# Reader32chv2.net
KiCad netlist of a schematic drawn in Altium Designer
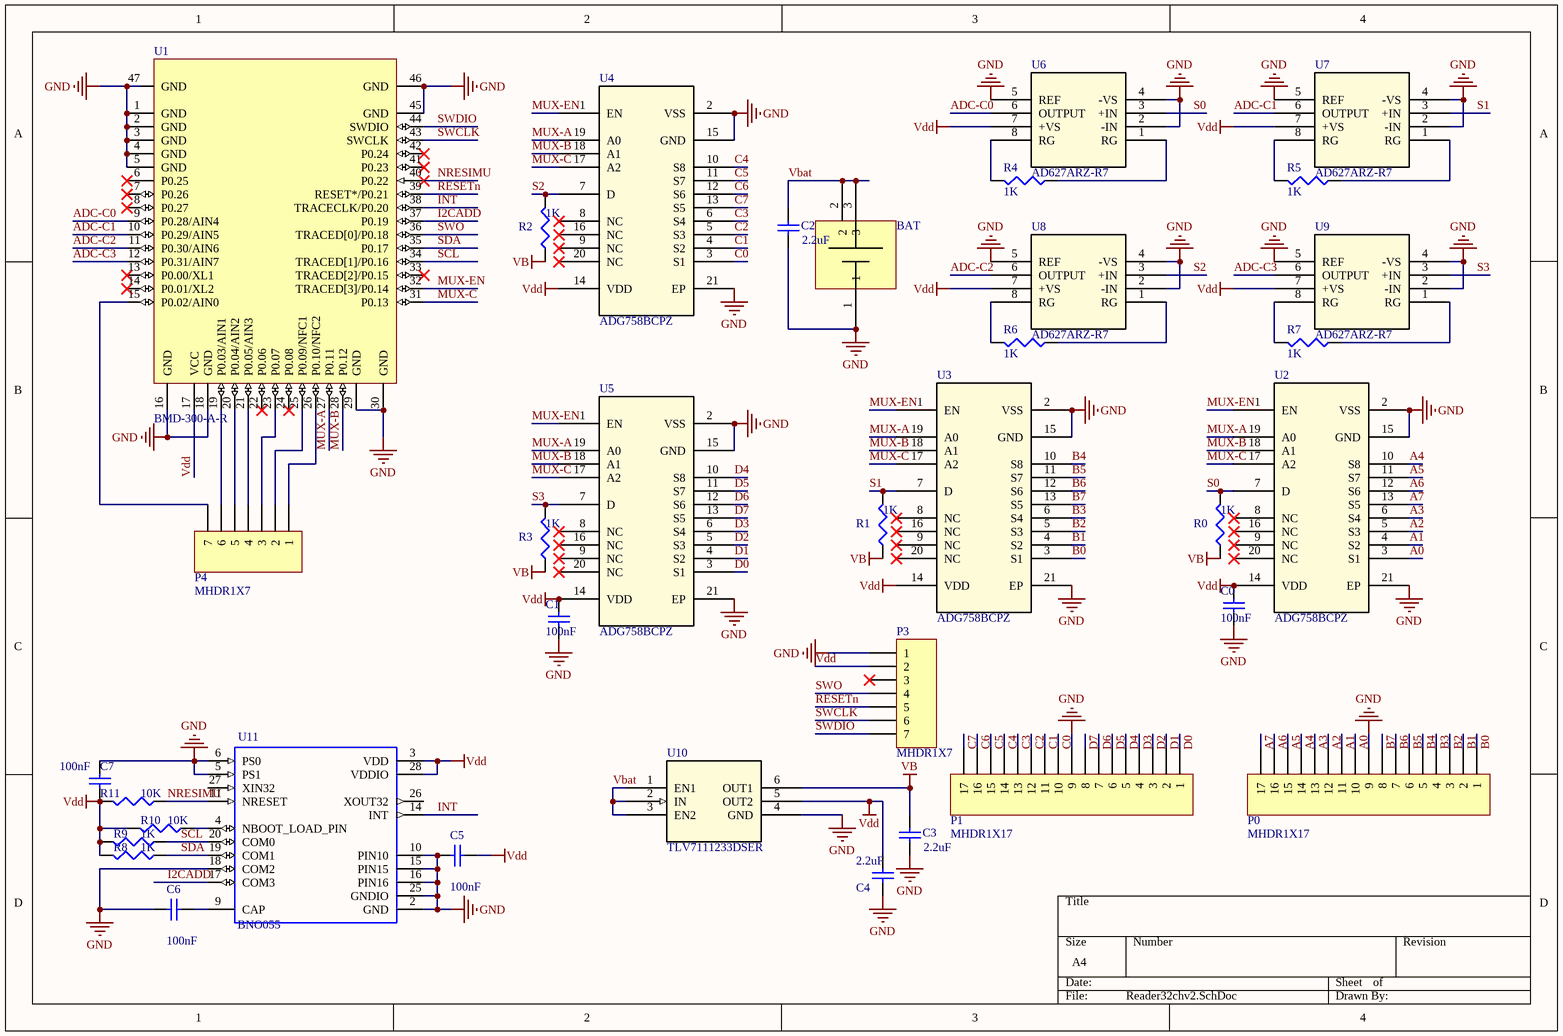
[diagram p0: Reader32chv2.SchDoc]

(export (version "E")
  (design (tool "Eeschema 10.0.6"))
  (components
    (comp (ref "BAT") (value "~") (footprint "BU-2032") (libsource (lib "My_Library") (part "BT")))
    (comp (ref "C0")
      (value "100nF")
      (footprint "1608[0603]")
      (description "Capacitor (Semiconductor SIM Model)")
      (fields (field (name "PUBLISHER") "Altium Limited"))
      (libsource (lib "Miscellaneous Devices") (part "Cap Semi"))
    )
    (comp (ref "C1")
      (value "100nF")
      (footprint "1608[0603]")
      (description "Capacitor (Semiconductor SIM Model)")
      (fields (field (name "PUBLISHER") "Altium Limited"))
      (libsource (lib "Miscellaneous Devices") (part "Cap Semi"))
    )
    (comp (ref "C2")
      (value "2.2uF")
      (footprint "1608[0603]")
      (description "Capacitor (Semiconductor SIM Model)")
      (fields (field (name "PUBLISHER") "Altium Limited"))
      (libsource (lib "Miscellaneous Devices") (part "Cap Semi"))
    )
    (comp (ref "C3")
      (value "2.2uF")
      (footprint "1608[0603]")
      (description "Capacitor (Semiconductor SIM Model)")
      (fields (field (name "PUBLISHER") "Altium Limited"))
      (libsource (lib "Miscellaneous Devices") (part "Cap Semi"))
    )
    (comp (ref "C4")
      (value "2.2uF")
      (footprint "1608[0603]")
      (description "Capacitor (Semiconductor SIM Model)")
      (fields (field (name "PUBLISHER") "Altium Limited"))
      (libsource (lib "Miscellaneous Devices") (part "Cap Semi"))
    )
    (comp (ref "C5")
      (value "100nF")
      (footprint "1608[0603]")
      (description "Capacitor (Semiconductor SIM Model)")
      (fields (field (name "PUBLISHER") "Altium Limited"))
      (libsource (lib "Miscellaneous Devices") (part "Cap Semi"))
    )
    (comp (ref "C6")
      (value "100nF")
      (footprint "1608[0603]")
      (description "Capacitor (Semiconductor SIM Model)")
      (fields (field (name "PUBLISHER") "Altium Limited"))
      (libsource (lib "Miscellaneous Devices") (part "Cap Semi"))
    )
    (comp (ref "C7")
      (value "100nF")
      (footprint "1608[0603]")
      (description "Capacitor (Semiconductor SIM Model)")
      (fields (field (name "PUBLISHER") "Altium Limited"))
      (libsource (lib "Miscellaneous Devices") (part "Cap Semi"))
    )
    (comp (ref "P0")
      (value "MHDR1X17")
      (footprint "MHDR1X17")
      (description "Header, 17-Pin")
      (fields (field (name "PUBLISHER") "Altium Limited"))
      (libsource (lib "Miscellaneous Connectors") (part "MHDR1X17"))
    )
    (comp (ref "P1")
      (value "MHDR1X17")
      (footprint "MHDR1X17")
      (description "Header, 17-Pin")
      (fields (field (name "PUBLISHER") "Altium Limited"))
      (libsource (lib "Miscellaneous Connectors") (part "MHDR1X17"))
    )
    (comp (ref "P3")
      (value "MHDR1X7")
      (footprint "MHDR1X7")
      (description "Header, 7-Pin")
      (fields (field (name "PUBLISHER") "Altium Limited"))
      (libsource (lib "Miscellaneous Connectors") (part "MHDR1X7"))
    )
    (comp (ref "P4")
      (value "MHDR1X7")
      (footprint "MHDR1X7")
      (description "Header, 7-Pin")
      (fields (field (name "PUBLISHER") "Altium Limited"))
      (libsource (lib "") (part "MHDR1X7_1"))
    )
    (comp (ref "R0")
      (value "1K")
      (footprint "J1-0603")
      (description "Resistor")
      (fields (field (name "PUBLISHER") "Altium Limited"))
      (libsource (lib "Miscellaneous Devices") (part "Res3"))
    )
    (comp (ref "R1")
      (value "1K")
      (footprint "J1-0603")
      (description "Resistor")
      (fields (field (name "PUBLISHER") "Altium Limited"))
      (libsource (lib "Miscellaneous Devices") (part "Res3"))
    )
    (comp (ref "R2")
      (value "1K")
      (footprint "J1-0603")
      (description "Resistor")
      (fields (field (name "PUBLISHER") "Altium Limited"))
      (libsource (lib "Miscellaneous Devices") (part "Res3"))
    )
    (comp (ref "R3")
      (value "1K")
      (footprint "J1-0603")
      (description "Resistor")
      (fields (field (name "PUBLISHER") "Altium Limited"))
      (libsource (lib "Miscellaneous Devices") (part "Res3"))
    )
    (comp (ref "R4")
      (value "1K")
      (footprint "J1-0603")
      (description "Resistor")
      (fields (field (name "PUBLISHER") "Altium Limited"))
      (libsource (lib "Miscellaneous Devices") (part "Res3"))
    )
    (comp (ref "R5")
      (value "1K")
      (footprint "J1-0603")
      (description "Resistor")
      (fields (field (name "PUBLISHER") "Altium Limited"))
      (libsource (lib "Miscellaneous Devices") (part "Res3"))
    )
    (comp (ref "R6")
      (value "1K")
      (footprint "J1-0603")
      (description "Resistor")
      (fields (field (name "PUBLISHER") "Altium Limited"))
      (libsource (lib "Miscellaneous Devices") (part "Res3"))
    )
    (comp (ref "R7")
      (value "1K")
      (footprint "J1-0603")
      (description "Resistor")
      (fields (field (name "PUBLISHER") "Altium Limited"))
      (libsource (lib "Miscellaneous Devices") (part "Res3"))
    )
    (comp (ref "R8")
      (value "1K")
      (footprint "J1-0603")
      (description "Resistor")
      (fields (field (name "PUBLISHER") "Altium Limited"))
      (libsource (lib "Miscellaneous Devices") (part "Res3"))
    )
    (comp (ref "R9")
      (value "1K")
      (footprint "J1-0603")
      (description "Resistor")
      (fields (field (name "PUBLISHER") "Altium Limited"))
      (libsource (lib "Miscellaneous Devices") (part "Res3"))
    )
    (comp (ref "R10")
      (value "10K")
      (footprint "J1-0603")
      (description "Resistor")
      (fields (field (name "PUBLISHER") "Altium Limited"))
      (libsource (lib "Miscellaneous Devices") (part "Res3"))
    )
    (comp (ref "R11")
      (value "10K")
      (footprint "J1-0603")
      (description "Resistor")
      (fields (field (name "PUBLISHER") "Altium Limited"))
      (libsource (lib "Miscellaneous Devices") (part "Res3"))
    )
    (comp (ref "U1")
      (value "BMD-300")
      (footprint "BMD-300")
      (description "Bluetooth 4.2 LE Module, nRF52832, 512kB Flash, 64kB RAM")
      (fields
        (field (name "PART NUMBER") "BMD-300-A")
        (field (name "MANUFACTURER") "Rigado")
        (field (name "MANUFACTURER P/N") "BMD-300-A-R")
        (field (name "ADDED BY") "Cam N")
      )
      (libsource (lib "BMD-300-Altium") (part "BMD-300-A"))
    )
    (comp (ref "U2")
      (value "ADG758BCPZ")
      (footprint "CP_20_6")
      (description "Imported")
      (libsource (lib "2017-12-08_19-39-35") (part "ADG758BCPZ"))
    )
    (comp (ref "U3")
      (value "ADG758BCPZ")
      (footprint "CP_20_6")
      (description "Imported")
      (libsource (lib "2017-12-08_19-39-35") (part "ADG758BCPZ"))
    )
    (comp (ref "U4")
      (value "ADG758BCPZ")
      (footprint "CP_20_6")
      (description "Imported")
      (libsource (lib "2017-12-08_19-39-35") (part "ADG758BCPZ"))
    )
    (comp (ref "U5")
      (value "ADG758BCPZ")
      (footprint "CP_20_6")
      (description "Imported")
      (libsource (lib "2017-12-08_19-39-35") (part "ADG758BCPZ"))
    )
    (comp (ref "U6")
      (value "AD627ARZ-R7")
      (footprint "AltiumDesigner:R_8")
      (description "Imported")
      (libsource (lib "AltiumDesigner") (part "AD627ARZ-R7"))
    )
    (comp (ref "U7")
      (value "AD627ARZ-R7")
      (footprint "AltiumDesigner:R_8")
      (description "Imported")
      (libsource (lib "AltiumDesigner") (part "AD627ARZ-R7"))
    )
    (comp (ref "U8")
      (value "AD627ARZ-R7")
      (footprint "AltiumDesigner:R_8")
      (description "Imported")
      (libsource (lib "AltiumDesigner") (part "AD627ARZ-R7"))
    )
    (comp (ref "U9")
      (value "AD627ARZ-R7")
      (footprint "AltiumDesigner:R_8")
      (description "Imported")
      (libsource (lib "AltiumDesigner") (part "AD627ARZ-R7"))
    )
    (comp (ref "U10")
      (value "TLV7111233DSER")
      (footprint "AltiumDesigner:DSE6")
      (description "Imported")
      (fields (field (name "MANUFACTURER") "Texas Instruments"))
      (libsource (lib "AltiumDesigner") (part "TLV7111233DSER"))
    )
    (comp (ref "U11")
      (value "BNO055")
      (footprint "LGA28R50P4X10_380X520X100")
      (description "BNO055 9-axis Absolute Orientation Sensor _ SiP _ w/Sensors and Sensor Fusion")
      (fields (field (name "MF") "Bosch"))
      (libsource (lib "BNO055") (part "BNO055"))
    )
  )
  (nets
    (net (code "1") (name "/A0") (class "Default")
      (node (ref "P0") (pin "10") (pinfunction "10_10") (pintype "passive"))
      (node (ref "U2") (pin "3") (pinfunction "S1_3") (pintype "passive"))
    )
    (net (code "2") (name "/A1") (class "Default")
      (node (ref "P0") (pin "11") (pinfunction "11_11") (pintype "passive"))
      (node (ref "U2") (pin "4") (pinfunction "S2_4") (pintype "passive"))
    )
    (net (code "3") (name "/A2") (class "Default")
      (node (ref "P0") (pin "12") (pinfunction "12_12") (pintype "passive"))
      (node (ref "U2") (pin "5") (pinfunction "S3_5") (pintype "passive"))
    )
    (net (code "4") (name "/A3") (class "Default")
      (node (ref "P0") (pin "13") (pinfunction "13_13") (pintype "passive"))
      (node (ref "U2") (pin "6") (pinfunction "S4_6") (pintype "passive"))
    )
    (net (code "5") (name "/A4") (class "Default")
      (node (ref "P0") (pin "14") (pinfunction "14_14") (pintype "passive"))
      (node (ref "U2") (pin "10") (pinfunction "S8_10") (pintype "passive"))
    )
    (net (code "6") (name "/A5") (class "Default")
      (node (ref "P0") (pin "15") (pinfunction "15_15") (pintype "passive"))
      (node (ref "U2") (pin "11") (pinfunction "S7_11") (pintype "passive"))
    )
    (net (code "7") (name "/A6") (class "Default")
      (node (ref "P0") (pin "16") (pinfunction "16_16") (pintype "passive"))
      (node (ref "U2") (pin "12") (pinfunction "S6_12") (pintype "passive"))
    )
    (net (code "8") (name "/A7") (class "Default")
      (node (ref "P0") (pin "17") (pinfunction "17_17") (pintype "passive"))
      (node (ref "U2") (pin "13") (pinfunction "S5_13") (pintype "passive"))
    )
    (net (code "9") (name "/ADC-C0") (class "Default")
      (node (ref "U1") (pin "9") (pinfunction "P0.28/AIN4_9") (pintype "bidirectional"))
      (node (ref "U6") (pin "6") (pinfunction "OUTPUT_6") (pintype "passive"))
    )
    (net (code "10") (name "/ADC-C1") (class "Default")
      (node (ref "U1") (pin "10") (pinfunction "P0.29/AIN5_10") (pintype "bidirectional"))
      (node (ref "U7") (pin "6") (pinfunction "OUTPUT_6") (pintype "passive"))
    )
    (net (code "11") (name "/ADC-C2") (class "Default")
      (node (ref "U1") (pin "11") (pinfunction "P0.30/AIN6_11") (pintype "bidirectional"))
      (node (ref "U8") (pin "6") (pinfunction "OUTPUT_6") (pintype "passive"))
    )
    (net (code "12") (name "/ADC-C3") (class "Default")
      (node (ref "U1") (pin "12") (pinfunction "P0.31/AIN7_12") (pintype "bidirectional"))
      (node (ref "U9") (pin "6") (pinfunction "OUTPUT_6") (pintype "passive"))
    )
    (net (code "13") (name "/B0") (class "Default")
      (node (ref "P0") (pin "1") (pinfunction "1_1") (pintype "passive"))
      (node (ref "U3") (pin "3") (pinfunction "S1_3") (pintype "passive"))
    )
    (net (code "14") (name "/B1") (class "Default")
      (node (ref "P0") (pin "2") (pinfunction "2_2") (pintype "passive"))
      (node (ref "U3") (pin "4") (pinfunction "S2_4") (pintype "passive"))
    )
    (net (code "15") (name "/B2") (class "Default")
      (node (ref "P0") (pin "3") (pinfunction "3_3") (pintype "passive"))
      (node (ref "U3") (pin "5") (pinfunction "S3_5") (pintype "passive"))
    )
    (net (code "16") (name "/B3") (class "Default")
      (node (ref "P0") (pin "4") (pinfunction "4_4") (pintype "passive"))
      (node (ref "U3") (pin "6") (pinfunction "S4_6") (pintype "passive"))
    )
    (net (code "17") (name "/B4") (class "Default")
      (node (ref "P0") (pin "5") (pinfunction "5_5") (pintype "passive"))
      (node (ref "U3") (pin "10") (pinfunction "S8_10") (pintype "passive"))
    )
    (net (code "18") (name "/B5") (class "Default")
      (node (ref "P0") (pin "6") (pinfunction "6_6") (pintype "passive"))
      (node (ref "U3") (pin "11") (pinfunction "S7_11") (pintype "passive"))
    )
    (net (code "19") (name "/B6") (class "Default")
      (node (ref "P0") (pin "7") (pinfunction "7_7") (pintype "passive"))
      (node (ref "U3") (pin "12") (pinfunction "S6_12") (pintype "passive"))
    )
    (net (code "20") (name "/B7") (class "Default")
      (node (ref "P0") (pin "8") (pinfunction "8_8") (pintype "passive"))
      (node (ref "U3") (pin "13") (pinfunction "S5_13") (pintype "passive"))
    )
    (net (code "21") (name "/C0") (class "Default")
      (node (ref "P1") (pin "10") (pinfunction "10_10") (pintype "passive"))
      (node (ref "U4") (pin "3") (pinfunction "S1_3") (pintype "passive"))
    )
    (net (code "22") (name "/C1") (class "Default")
      (node (ref "P1") (pin "11") (pinfunction "11_11") (pintype "passive"))
      (node (ref "U4") (pin "4") (pinfunction "S2_4") (pintype "passive"))
    )
    (net (code "23") (name "/C2") (class "Default")
      (node (ref "P1") (pin "12") (pinfunction "12_12") (pintype "passive"))
      (node (ref "U4") (pin "5") (pinfunction "S3_5") (pintype "passive"))
    )
    (net (code "24") (name "/C3") (class "Default")
      (node (ref "P1") (pin "13") (pinfunction "13_13") (pintype "passive"))
      (node (ref "U4") (pin "6") (pinfunction "S4_6") (pintype "passive"))
    )
    (net (code "25") (name "/C4") (class "Default")
      (node (ref "P1") (pin "14") (pinfunction "14_14") (pintype "passive"))
      (node (ref "U4") (pin "10") (pinfunction "S8_10") (pintype "passive"))
    )
    (net (code "26") (name "/C5") (class "Default")
      (node (ref "P1") (pin "15") (pinfunction "15_15") (pintype "passive"))
      (node (ref "U4") (pin "11") (pinfunction "S7_11") (pintype "passive"))
    )
    (net (code "27") (name "/C6") (class "Default")
      (node (ref "P1") (pin "16") (pinfunction "16_16") (pintype "passive"))
      (node (ref "U4") (pin "12") (pinfunction "S6_12") (pintype "passive"))
    )
    (net (code "28") (name "/C7") (class "Default")
      (node (ref "P1") (pin "17") (pinfunction "17_17") (pintype "passive"))
      (node (ref "U4") (pin "13") (pinfunction "S5_13") (pintype "passive"))
    )
    (net (code "29") (name "/D0") (class "Default")
      (node (ref "P1") (pin "1") (pinfunction "1_1") (pintype "passive"))
      (node (ref "U5") (pin "3") (pinfunction "S1_3") (pintype "passive"))
    )
    (net (code "30") (name "/D1") (class "Default")
      (node (ref "P1") (pin "2") (pinfunction "2_2") (pintype "passive"))
      (node (ref "U5") (pin "4") (pinfunction "S2_4") (pintype "passive"))
    )
    (net (code "31") (name "/D2") (class "Default")
      (node (ref "P1") (pin "3") (pinfunction "3_3") (pintype "passive"))
      (node (ref "U5") (pin "5") (pinfunction "S3_5") (pintype "passive"))
    )
    (net (code "32") (name "/D3") (class "Default")
      (node (ref "P1") (pin "4") (pinfunction "4_4") (pintype "passive"))
      (node (ref "U5") (pin "6") (pinfunction "S4_6") (pintype "passive"))
    )
    (net (code "33") (name "/D4") (class "Default")
      (node (ref "P1") (pin "5") (pinfunction "5_5") (pintype "passive"))
      (node (ref "U5") (pin "10") (pinfunction "S8_10") (pintype "passive"))
    )
    (net (code "34") (name "/D5") (class "Default")
      (node (ref "P1") (pin "6") (pinfunction "6_6") (pintype "passive"))
      (node (ref "U5") (pin "11") (pinfunction "S7_11") (pintype "passive"))
    )
    (net (code "35") (name "/D6") (class "Default")
      (node (ref "P1") (pin "7") (pinfunction "7_7") (pintype "passive"))
      (node (ref "U5") (pin "12") (pinfunction "S6_12") (pintype "passive"))
    )
    (net (code "36") (name "/D7") (class "Default")
      (node (ref "P1") (pin "8") (pinfunction "8_8") (pintype "passive"))
      (node (ref "U5") (pin "13") (pinfunction "S5_13") (pintype "passive"))
    )
    (net (code "37") (name "/I2CADD") (class "Default")
      (node (ref "U1") (pin "37") (pinfunction "P0.19_37") (pintype "bidirectional"))
      (node (ref "U11") (pin "17") (pinfunction "COM3_17") (pintype "bidirectional"))
    )
    (net (code "38") (name "/INT") (class "Default")
      (node (ref "U1") (pin "38") (pinfunction "TRACECLK/P0.20_38") (pintype "bidirectional"))
      (node (ref "U11") (pin "14") (pinfunction "INT_14") (pintype "output"))
    )
    (net (code "39") (name "/MUX-A") (class "Default")
      (node (ref "U1") (pin "27") (pinfunction "P0.11_27") (pintype "bidirectional"))
      (node (ref "U2") (pin "19") (pinfunction "A0_19") (pintype "passive"))
      (node (ref "U3") (pin "19") (pinfunction "A0_19") (pintype "passive"))
      (node (ref "U4") (pin "19") (pinfunction "A0_19") (pintype "passive"))
      (node (ref "U5") (pin "19") (pinfunction "A0_19") (pintype "passive"))
    )
    (net (code "40") (name "/MUX-B") (class "Default")
      (node (ref "U1") (pin "28") (pinfunction "P0.12_28") (pintype "bidirectional"))
      (node (ref "U2") (pin "18") (pinfunction "A1_18") (pintype "passive"))
      (node (ref "U3") (pin "18") (pinfunction "A1_18") (pintype "passive"))
      (node (ref "U4") (pin "18") (pinfunction "A1_18") (pintype "passive"))
      (node (ref "U5") (pin "18") (pinfunction "A1_18") (pintype "passive"))
    )
    (net (code "41") (name "/MUX-C") (class "Default")
      (node (ref "U1") (pin "31") (pinfunction "P0.13_31") (pintype "bidirectional"))
      (node (ref "U2") (pin "17") (pinfunction "A2_17") (pintype "passive"))
      (node (ref "U3") (pin "17") (pinfunction "A2_17") (pintype "passive"))
      (node (ref "U4") (pin "17") (pinfunction "A2_17") (pintype "passive"))
      (node (ref "U5") (pin "17") (pinfunction "A2_17") (pintype "passive"))
    )
    (net (code "42") (name "/MUX-EN") (class "Default")
      (node (ref "U1") (pin "32") (pinfunction "TRACED[3]/P0.14_32") (pintype "bidirectional"))
      (node (ref "U2") (pin "1") (pinfunction "EN_1") (pintype "passive"))
      (node (ref "U3") (pin "1") (pinfunction "EN_1") (pintype "passive"))
      (node (ref "U4") (pin "1") (pinfunction "EN_1") (pintype "passive"))
      (node (ref "U5") (pin "1") (pinfunction "EN_1") (pintype "passive"))
    )
    (net (code "43") (name "/NRESIMU") (class "Default")
      (node (ref "R11") (pin "1") (pinfunction "1_1") (pintype "passive"))
      (node (ref "U1") (pin "40") (pinfunction "P0.22_40") (pintype "input"))
      (node (ref "U11") (pin "11") (pinfunction "NRESET_11") (pintype "input"))
    )
    (net (code "44") (name "/RESETn") (class "Default")
      (node (ref "P3") (pin "5") (pinfunction "5_5") (pintype "passive"))
      (node (ref "U1") (pin "39") (pinfunction "RESET*/P0.21_39") (pintype "bidirectional"))
    )
    (net (code "45") (name "/S0") (class "Default")
      (node (ref "R0") (pin "2") (pinfunction "2_2") (pintype "passive"))
      (node (ref "U2") (pin "7") (pinfunction "D_7") (pintype "passive"))
      (node (ref "U6") (pin "3") (pinfunction "+IN_3") (pintype "passive"))
    )
    (net (code "46") (name "/S1") (class "Default")
      (node (ref "R1") (pin "2") (pinfunction "2_2") (pintype "passive"))
      (node (ref "U3") (pin "7") (pinfunction "D_7") (pintype "passive"))
      (node (ref "U7") (pin "3") (pinfunction "+IN_3") (pintype "passive"))
    )
    (net (code "47") (name "/S2") (class "Default")
      (node (ref "R2") (pin "2") (pinfunction "2_2") (pintype "passive"))
      (node (ref "U4") (pin "7") (pinfunction "D_7") (pintype "passive"))
      (node (ref "U8") (pin "3") (pinfunction "+IN_3") (pintype "passive"))
    )
    (net (code "48") (name "/S3") (class "Default")
      (node (ref "R3") (pin "2") (pinfunction "2_2") (pintype "passive"))
      (node (ref "U5") (pin "7") (pinfunction "D_7") (pintype "passive"))
      (node (ref "U9") (pin "3") (pinfunction "+IN_3") (pintype "passive"))
    )
    (net (code "49") (name "/SCL") (class "Default")
      (node (ref "R9") (pin "1") (pinfunction "1_1") (pintype "passive"))
      (node (ref "U1") (pin "34") (pinfunction "TRACED[1]/P0.16_34") (pintype "bidirectional"))
      (node (ref "U11") (pin "20") (pinfunction "COM0_20") (pintype "bidirectional"))
    )
    (net (code "50") (name "/SDA") (class "Default")
      (node (ref "R8") (pin "1") (pinfunction "1_1") (pintype "passive"))
      (node (ref "U1") (pin "35") (pinfunction "P0.17_35") (pintype "bidirectional"))
      (node (ref "U11") (pin "19") (pinfunction "COM1_19") (pintype "bidirectional"))
    )
    (net (code "51") (name "/SWCLK") (class "Default")
      (node (ref "P3") (pin "6") (pinfunction "6_6") (pintype "passive"))
      (node (ref "U1") (pin "43") (pinfunction "SWCLK_43") (pintype "bidirectional"))
    )
    (net (code "52") (name "/SWDIO") (class "Default")
      (node (ref "P3") (pin "7") (pinfunction "7_7") (pintype "passive"))
      (node (ref "U1") (pin "44") (pinfunction "SWDIO_44") (pintype "bidirectional"))
    )
    (net (code "53") (name "/SWO") (class "Default")
      (node (ref "P3") (pin "4") (pinfunction "4_4") (pintype "passive"))
      (node (ref "U1") (pin "36") (pinfunction "TRACED[0]/P0.18_36") (pintype "bidirectional"))
    )
    (net (code "54") (name "/Vbat") (class "Default")
      (node (ref "BAT") (pin "2") (pinfunction "2_2") (pintype "passive"))
      (node (ref "BAT") (pin "3") (pinfunction "3_3") (pintype "passive"))
      (node (ref "C2") (pin "2") (pinfunction "2_2") (pintype "passive"))
      (node (ref "U10") (pin "1") (pinfunction "EN1_1") (pintype "passive"))
      (node (ref "U10") (pin "2") (pinfunction "IN_2") (pintype "input"))
      (node (ref "U10") (pin "3") (pinfunction "EN2_3") (pintype "passive"))
    )
    (net (code "55") (name "GND") (class "Default")
      (node (ref "BAT") (pin "1") (pinfunction "1_1") (pintype "passive"))
      (node (ref "C0") (pin "2") (pinfunction "2_2") (pintype "passive"))
      (node (ref "C1") (pin "2") (pinfunction "2_2") (pintype "passive"))
      (node (ref "C2") (pin "1") (pinfunction "1_1") (pintype "passive"))
      (node (ref "C3") (pin "1") (pinfunction "1_1") (pintype "passive"))
      (node (ref "C4") (pin "1") (pinfunction "1_1") (pintype "passive"))
      (node (ref "C5") (pin "1") (pinfunction "1_1") (pintype "passive"))
      (node (ref "C6") (pin "1") (pinfunction "1_1") (pintype "passive"))
      (node (ref "C7") (pin "1") (pinfunction "1_1") (pintype "passive"))
      (node (ref "P0") (pin "9") (pinfunction "9_9") (pintype "passive"))
      (node (ref "P1") (pin "9") (pinfunction "9_9") (pintype "passive"))
      (node (ref "P3") (pin "1") (pinfunction "1_1") (pintype "passive"))
      (node (ref "U1") (pin "1") (pinfunction "GND_1") (pintype "power_in"))
      (node (ref "U1") (pin "16") (pinfunction "GND_16") (pintype "power_in"))
      (node (ref "U1") (pin "18") (pinfunction "GND_18") (pintype "power_in"))
      (node (ref "U1") (pin "2") (pinfunction "GND_2") (pintype "power_in"))
      (node (ref "U1") (pin "29") (pinfunction "GND_29") (pintype "power_in"))
      (node (ref "U1") (pin "3") (pinfunction "GND_3") (pintype "power_in"))
      (node (ref "U1") (pin "30") (pinfunction "GND_30") (pintype "power_in"))
      (node (ref "U1") (pin "4") (pinfunction "GND_4") (pintype "power_in"))
      (node (ref "U1") (pin "45") (pinfunction "GND_45") (pintype "power_in"))
      (node (ref "U1") (pin "46") (pinfunction "GND_46") (pintype "power_in"))
      (node (ref "U1") (pin "47") (pinfunction "GND_47") (pintype "power_in"))
      (node (ref "U1") (pin "5") (pinfunction "GND_5") (pintype "power_in"))
      (node (ref "U10") (pin "4") (pinfunction "GND_4") (pintype "power_in"))
      (node (ref "U11") (pin "10") (pinfunction "PIN10_10") (pintype "power_in"))
      (node (ref "U11") (pin "15") (pinfunction "PIN15_15") (pintype "power_in"))
      (node (ref "U11") (pin "16") (pinfunction "PIN16_16") (pintype "power_in"))
      (node (ref "U11") (pin "18") (pinfunction "COM2_18") (pintype "bidirectional"))
      (node (ref "U11") (pin "2") (pinfunction "GND_2") (pintype "power_in"))
      (node (ref "U11") (pin "25") (pinfunction "GNDIO_25") (pintype "power_in"))
      (node (ref "U11") (pin "5") (pinfunction "PS1_5") (pintype "input"))
      (node (ref "U11") (pin "6") (pinfunction "PS0_6") (pintype "input"))
      (node (ref "U2") (pin "15") (pinfunction "GND_15") (pintype "passive"))
      (node (ref "U2") (pin "2") (pinfunction "VSS_2") (pintype "power_in"))
      (node (ref "U2") (pin "21") (pinfunction "EP_21") (pintype "passive"))
      (node (ref "U3") (pin "15") (pinfunction "GND_15") (pintype "passive"))
      (node (ref "U3") (pin "2") (pinfunction "VSS_2") (pintype "power_in"))
      (node (ref "U3") (pin "21") (pinfunction "EP_21") (pintype "passive"))
      (node (ref "U4") (pin "15") (pinfunction "GND_15") (pintype "passive"))
      (node (ref "U4") (pin "2") (pinfunction "VSS_2") (pintype "power_in"))
      (node (ref "U4") (pin "21") (pinfunction "EP_21") (pintype "passive"))
      (node (ref "U5") (pin "15") (pinfunction "GND_15") (pintype "passive"))
      (node (ref "U5") (pin "2") (pinfunction "VSS_2") (pintype "power_in"))
      (node (ref "U5") (pin "21") (pinfunction "EP_21") (pintype "passive"))
      (node (ref "U6") (pin "2") (pinfunction "-IN_2") (pintype "passive"))
      (node (ref "U6") (pin "4") (pinfunction "-VS_4") (pintype "power_in"))
      (node (ref "U6") (pin "5") (pinfunction "REF_5") (pintype "passive"))
      (node (ref "U7") (pin "2") (pinfunction "-IN_2") (pintype "passive"))
      (node (ref "U7") (pin "4") (pinfunction "-VS_4") (pintype "power_in"))
      (node (ref "U7") (pin "5") (pinfunction "REF_5") (pintype "passive"))
      (node (ref "U8") (pin "2") (pinfunction "-IN_2") (pintype "passive"))
      (node (ref "U8") (pin "4") (pinfunction "-VS_4") (pintype "power_in"))
      (node (ref "U8") (pin "5") (pinfunction "REF_5") (pintype "passive"))
      (node (ref "U9") (pin "2") (pinfunction "-IN_2") (pintype "passive"))
      (node (ref "U9") (pin "4") (pinfunction "-VS_4") (pintype "power_in"))
      (node (ref "U9") (pin "5") (pinfunction "REF_5") (pintype "passive"))
    )
    (net (code "56") (name "Net-(R4-Pad1)") (class "Default")
      (node (ref "R4") (pin "1") (pinfunction "1_1") (pintype "passive"))
      (node (ref "U6") (pin "1") (pinfunction "RG_1") (pintype "passive"))
    )
    (net (code "57") (name "Net-(R4-Pad2)") (class "Default")
      (node (ref "R4") (pin "2") (pinfunction "2_2") (pintype "passive"))
      (node (ref "U6") (pin "8") (pinfunction "RG_8") (pintype "passive"))
    )
    (net (code "58") (name "Net-(R5-Pad1)") (class "Default")
      (node (ref "R5") (pin "1") (pinfunction "1_1") (pintype "passive"))
      (node (ref "U7") (pin "1") (pinfunction "RG_1") (pintype "passive"))
    )
    (net (code "59") (name "Net-(R5-Pad2)") (class "Default")
      (node (ref "R5") (pin "2") (pinfunction "2_2") (pintype "passive"))
      (node (ref "U7") (pin "8") (pinfunction "RG_8") (pintype "passive"))
    )
    (net (code "60") (name "Net-(R6-Pad1)") (class "Default")
      (node (ref "R6") (pin "1") (pinfunction "1_1") (pintype "passive"))
      (node (ref "U8") (pin "1") (pinfunction "RG_1") (pintype "passive"))
    )
    (net (code "61") (name "Net-(R6-Pad2)") (class "Default")
      (node (ref "R6") (pin "2") (pinfunction "2_2") (pintype "passive"))
      (node (ref "U8") (pin "8") (pinfunction "RG_8") (pintype "passive"))
    )
    (net (code "62") (name "Net-(R7-Pad1)") (class "Default")
      (node (ref "R7") (pin "1") (pinfunction "1_1") (pintype "passive"))
      (node (ref "U9") (pin "1") (pinfunction "RG_1") (pintype "passive"))
    )
    (net (code "63") (name "Net-(R7-Pad2)") (class "Default")
      (node (ref "R7") (pin "2") (pinfunction "2_2") (pintype "passive"))
      (node (ref "U9") (pin "8") (pinfunction "RG_8") (pintype "passive"))
    )
    (net (code "64") (name "Net-(U1-P0.02{slash}AIN0)") (class "Default")
      (node (ref "P4") (pin "7") (pinfunction "7_7") (pintype "passive"))
      (node (ref "U1") (pin "15") (pinfunction "P0.02/AIN0_15") (pintype "bidirectional"))
    )
    (net (code "65") (name "Net-(U1-P0.03{slash}AIN1)") (class "Default")
      (node (ref "P4") (pin "6") (pinfunction "6_6") (pintype "passive"))
      (node (ref "U1") (pin "19") (pinfunction "P0.03/AIN1_19") (pintype "bidirectional"))
    )
    (net (code "66") (name "Net-(U1-P0.04{slash}AIN2)") (class "Default")
      (node (ref "P4") (pin "5") (pinfunction "5_5") (pintype "passive"))
      (node (ref "U1") (pin "20") (pinfunction "P0.04/AIN2_20") (pintype "bidirectional"))
    )
    (net (code "67") (name "Net-(U1-P0.05{slash}AIN3)") (class "Default")
      (node (ref "P4") (pin "4") (pinfunction "4_4") (pintype "passive"))
      (node (ref "U1") (pin "21") (pinfunction "P0.05/AIN3_21") (pintype "bidirectional"))
    )
    (net (code "68") (name "Net-(U1-P0.07)") (class "Default")
      (node (ref "P4") (pin "3") (pinfunction "3_3") (pintype "passive"))
      (node (ref "U1") (pin "23") (pinfunction "P0.07_23") (pintype "bidirectional"))
    )
    (net (code "69") (name "Net-(U1-P0.09{slash}NFC1)") (class "Default")
      (node (ref "P4") (pin "2") (pinfunction "2_2") (pintype "passive"))
      (node (ref "U1") (pin "25") (pinfunction "P0.09/NFC1_25") (pintype "bidirectional"))
    )
    (net (code "70") (name "Net-(U1-P0.10{slash}NFC2)") (class "Default")
      (node (ref "P4") (pin "1") (pinfunction "1_1") (pintype "passive"))
      (node (ref "U1") (pin "26") (pinfunction "P0.10/NFC2_26") (pintype "bidirectional"))
    )
    (net (code "71") (name "Net-(U11-CAP)") (class "Default")
      (node (ref "C6") (pin "2") (pinfunction "2_2") (pintype "passive"))
      (node (ref "U11") (pin "9") (pinfunction "CAP_9") (pintype "passive"))
    )
    (net (code "72") (name "Net-(U11-NBOOT_LOAD_PIN)") (class "Default")
      (node (ref "R10") (pin "1") (pinfunction "1_1") (pintype "passive"))
      (node (ref "U11") (pin "4") (pinfunction "NBOOT_LOAD_PIN_4") (pintype "bidirectional"))
    )
    (net (code "73") (name "VB") (class "Default")
      (node (ref "C3") (pin "2") (pinfunction "2_2") (pintype "passive"))
      (node (ref "R0") (pin "1") (pinfunction "1_1") (pintype "passive"))
      (node (ref "R1") (pin "1") (pinfunction "1_1") (pintype "passive"))
      (node (ref "R2") (pin "1") (pinfunction "1_1") (pintype "passive"))
      (node (ref "R3") (pin "1") (pinfunction "1_1") (pintype "passive"))
      (node (ref "U10") (pin "6") (pinfunction "OUT1_6") (pintype "power_in"))
    )
    (net (code "74") (name "Vdd") (class "Default")
      (node (ref "C0") (pin "1") (pinfunction "1_1") (pintype "passive"))
      (node (ref "C1") (pin "1") (pinfunction "1_1") (pintype "passive"))
      (node (ref "C4") (pin "2") (pinfunction "2_2") (pintype "passive"))
      (node (ref "C5") (pin "2") (pinfunction "2_2") (pintype "passive"))
      (node (ref "C7") (pin "2") (pinfunction "2_2") (pintype "passive"))
      (node (ref "P3") (pin "2") (pinfunction "2_2") (pintype "passive"))
      (node (ref "R10") (pin "2") (pinfunction "2_2") (pintype "passive"))
      (node (ref "R11") (pin "2") (pinfunction "2_2") (pintype "passive"))
      (node (ref "R8") (pin "2") (pinfunction "2_2") (pintype "passive"))
      (node (ref "R9") (pin "2") (pinfunction "2_2") (pintype "passive"))
      (node (ref "U1") (pin "17") (pinfunction "VCC_17") (pintype "power_in"))
      (node (ref "U10") (pin "5") (pinfunction "OUT2_5") (pintype "power_in"))
      (node (ref "U11") (pin "28") (pinfunction "VDDIO_28") (pintype "power_in"))
      (node (ref "U11") (pin "3") (pinfunction "VDD_3") (pintype "power_in"))
      (node (ref "U2") (pin "14") (pinfunction "VDD_14") (pintype "power_in"))
      (node (ref "U3") (pin "14") (pinfunction "VDD_14") (pintype "power_in"))
      (node (ref "U4") (pin "14") (pinfunction "VDD_14") (pintype "power_in"))
      (node (ref "U5") (pin "14") (pinfunction "VDD_14") (pintype "power_in"))
      (node (ref "U6") (pin "7") (pinfunction "+VS_7") (pintype "power_in"))
      (node (ref "U7") (pin "7") (pinfunction "+VS_7") (pintype "power_in"))
      (node (ref "U8") (pin "7") (pinfunction "+VS_7") (pintype "power_in"))
      (node (ref "U9") (pin "7") (pinfunction "+VS_7") (pintype "power_in"))
    )
    (net (code "75") (name "unconnected-(P3-Pad3)") (class "Default")
      (node (ref "P3") (pin "3") (pinfunction "3_3") (pintype "passive+no_connect"))
    )
    (net (code "76") (name "unconnected-(U1-P0.00{slash}XL1-Pad13)") (class "Default")
      (node (ref "U1") (pin "13") (pinfunction "P0.00/XL1_13") (pintype "bidirectional+no_connect"))
    )
    (net (code "77") (name "unconnected-(U1-P0.01{slash}XL2-Pad14)") (class "Default")
      (node (ref "U1") (pin "14") (pinfunction "P0.01/XL2_14") (pintype "bidirectional+no_connect"))
    )
    (net (code "78") (name "unconnected-(U1-P0.06-Pad22)") (class "Default")
      (node (ref "U1") (pin "22") (pinfunction "P0.06_22") (pintype "bidirectional+no_connect"))
    )
    (net (code "79") (name "unconnected-(U1-P0.08-Pad24)") (class "Default")
      (node (ref "U1") (pin "24") (pinfunction "P0.08_24") (pintype "bidirectional+no_connect"))
    )
    (net (code "80") (name "unconnected-(U1-P0.23-Pad41)") (class "Default")
      (node (ref "U1") (pin "41") (pinfunction "P0.23_41") (pintype "bidirectional+no_connect"))
    )
    (net (code "81") (name "unconnected-(U1-P0.24-Pad42)") (class "Default")
      (node (ref "U1") (pin "42") (pinfunction "P0.24_42") (pintype "bidirectional+no_connect"))
    )
    (net (code "82") (name "unconnected-(U1-P0.25-Pad6)") (class "Default")
      (node (ref "U1") (pin "6") (pinfunction "P0.25_6") (pintype "power_in+no_connect"))
    )
    (net (code "83") (name "unconnected-(U1-P0.26-Pad7)") (class "Default")
      (node (ref "U1") (pin "7") (pinfunction "P0.26_7") (pintype "bidirectional+no_connect"))
    )
    (net (code "84") (name "unconnected-(U1-P0.27-Pad8)") (class "Default")
      (node (ref "U1") (pin "8") (pinfunction "P0.27_8") (pintype "bidirectional+no_connect"))
    )
    (net (code "85") (name "unconnected-(U1-TRACED[2]{slash}P0.15-Pad33)") (class "Default")
      (node (ref "U1") (pin "33") (pinfunction "TRACED[2]/P0.15_33") (pintype "bidirectional+no_connect"))
    )
    (net (code "86") (name "unconnected-(U2-NC-Pad8)") (class "Default")
      (node (ref "U2") (pin "8") (pinfunction "NC_8") (pintype "passive+no_connect"))
    )
    (net (code "87") (name "unconnected-(U2-NC-Pad9)") (class "Default")
      (node (ref "U2") (pin "9") (pinfunction "NC_9") (pintype "passive+no_connect"))
    )
    (net (code "88") (name "unconnected-(U2-NC-Pad16)") (class "Default")
      (node (ref "U2") (pin "16") (pinfunction "NC_16") (pintype "passive+no_connect"))
    )
    (net (code "89") (name "unconnected-(U2-NC-Pad20)") (class "Default")
      (node (ref "U2") (pin "20") (pinfunction "NC_20") (pintype "passive+no_connect"))
    )
    (net (code "90") (name "unconnected-(U3-NC-Pad8)") (class "Default")
      (node (ref "U3") (pin "8") (pinfunction "NC_8") (pintype "passive+no_connect"))
    )
    (net (code "91") (name "unconnected-(U3-NC-Pad9)") (class "Default")
      (node (ref "U3") (pin "9") (pinfunction "NC_9") (pintype "passive+no_connect"))
    )
    (net (code "92") (name "unconnected-(U3-NC-Pad16)") (class "Default")
      (node (ref "U3") (pin "16") (pinfunction "NC_16") (pintype "passive+no_connect"))
    )
    (net (code "93") (name "unconnected-(U3-NC-Pad20)") (class "Default")
      (node (ref "U3") (pin "20") (pinfunction "NC_20") (pintype "passive+no_connect"))
    )
    (net (code "94") (name "unconnected-(U4-NC-Pad8)") (class "Default")
      (node (ref "U4") (pin "8") (pinfunction "NC_8") (pintype "passive+no_connect"))
    )
    (net (code "95") (name "unconnected-(U4-NC-Pad9)") (class "Default")
      (node (ref "U4") (pin "9") (pinfunction "NC_9") (pintype "passive+no_connect"))
    )
    (net (code "96") (name "unconnected-(U4-NC-Pad16)") (class "Default")
      (node (ref "U4") (pin "16") (pinfunction "NC_16") (pintype "passive+no_connect"))
    )
    (net (code "97") (name "unconnected-(U4-NC-Pad20)") (class "Default")
      (node (ref "U4") (pin "20") (pinfunction "NC_20") (pintype "passive+no_connect"))
    )
    (net (code "98") (name "unconnected-(U5-NC-Pad8)") (class "Default")
      (node (ref "U5") (pin "8") (pinfunction "NC_8") (pintype "passive+no_connect"))
    )
    (net (code "99") (name "unconnected-(U5-NC-Pad9)") (class "Default")
      (node (ref "U5") (pin "9") (pinfunction "NC_9") (pintype "passive+no_connect"))
    )
    (net (code "100") (name "unconnected-(U5-NC-Pad16)") (class "Default")
      (node (ref "U5") (pin "16") (pinfunction "NC_16") (pintype "passive+no_connect"))
    )
    (net (code "101") (name "unconnected-(U5-NC-Pad20)") (class "Default")
      (node (ref "U5") (pin "20") (pinfunction "NC_20") (pintype "passive+no_connect"))
    )
    (net (code "102") (name "unconnected-(U11-XIN32-Pad27)") (class "Default")
      (node (ref "U11") (pin "27") (pinfunction "XIN32_27") (pintype "input"))
    )
    (net (code "103") (name "unconnected-(U11-XOUT32-Pad26)") (class "Default")
      (node (ref "U11") (pin "26") (pinfunction "XOUT32_26") (pintype "output"))
    )
  )
)
